# Top.net
KiCad netlist of a schematic drawn in Altium Designer
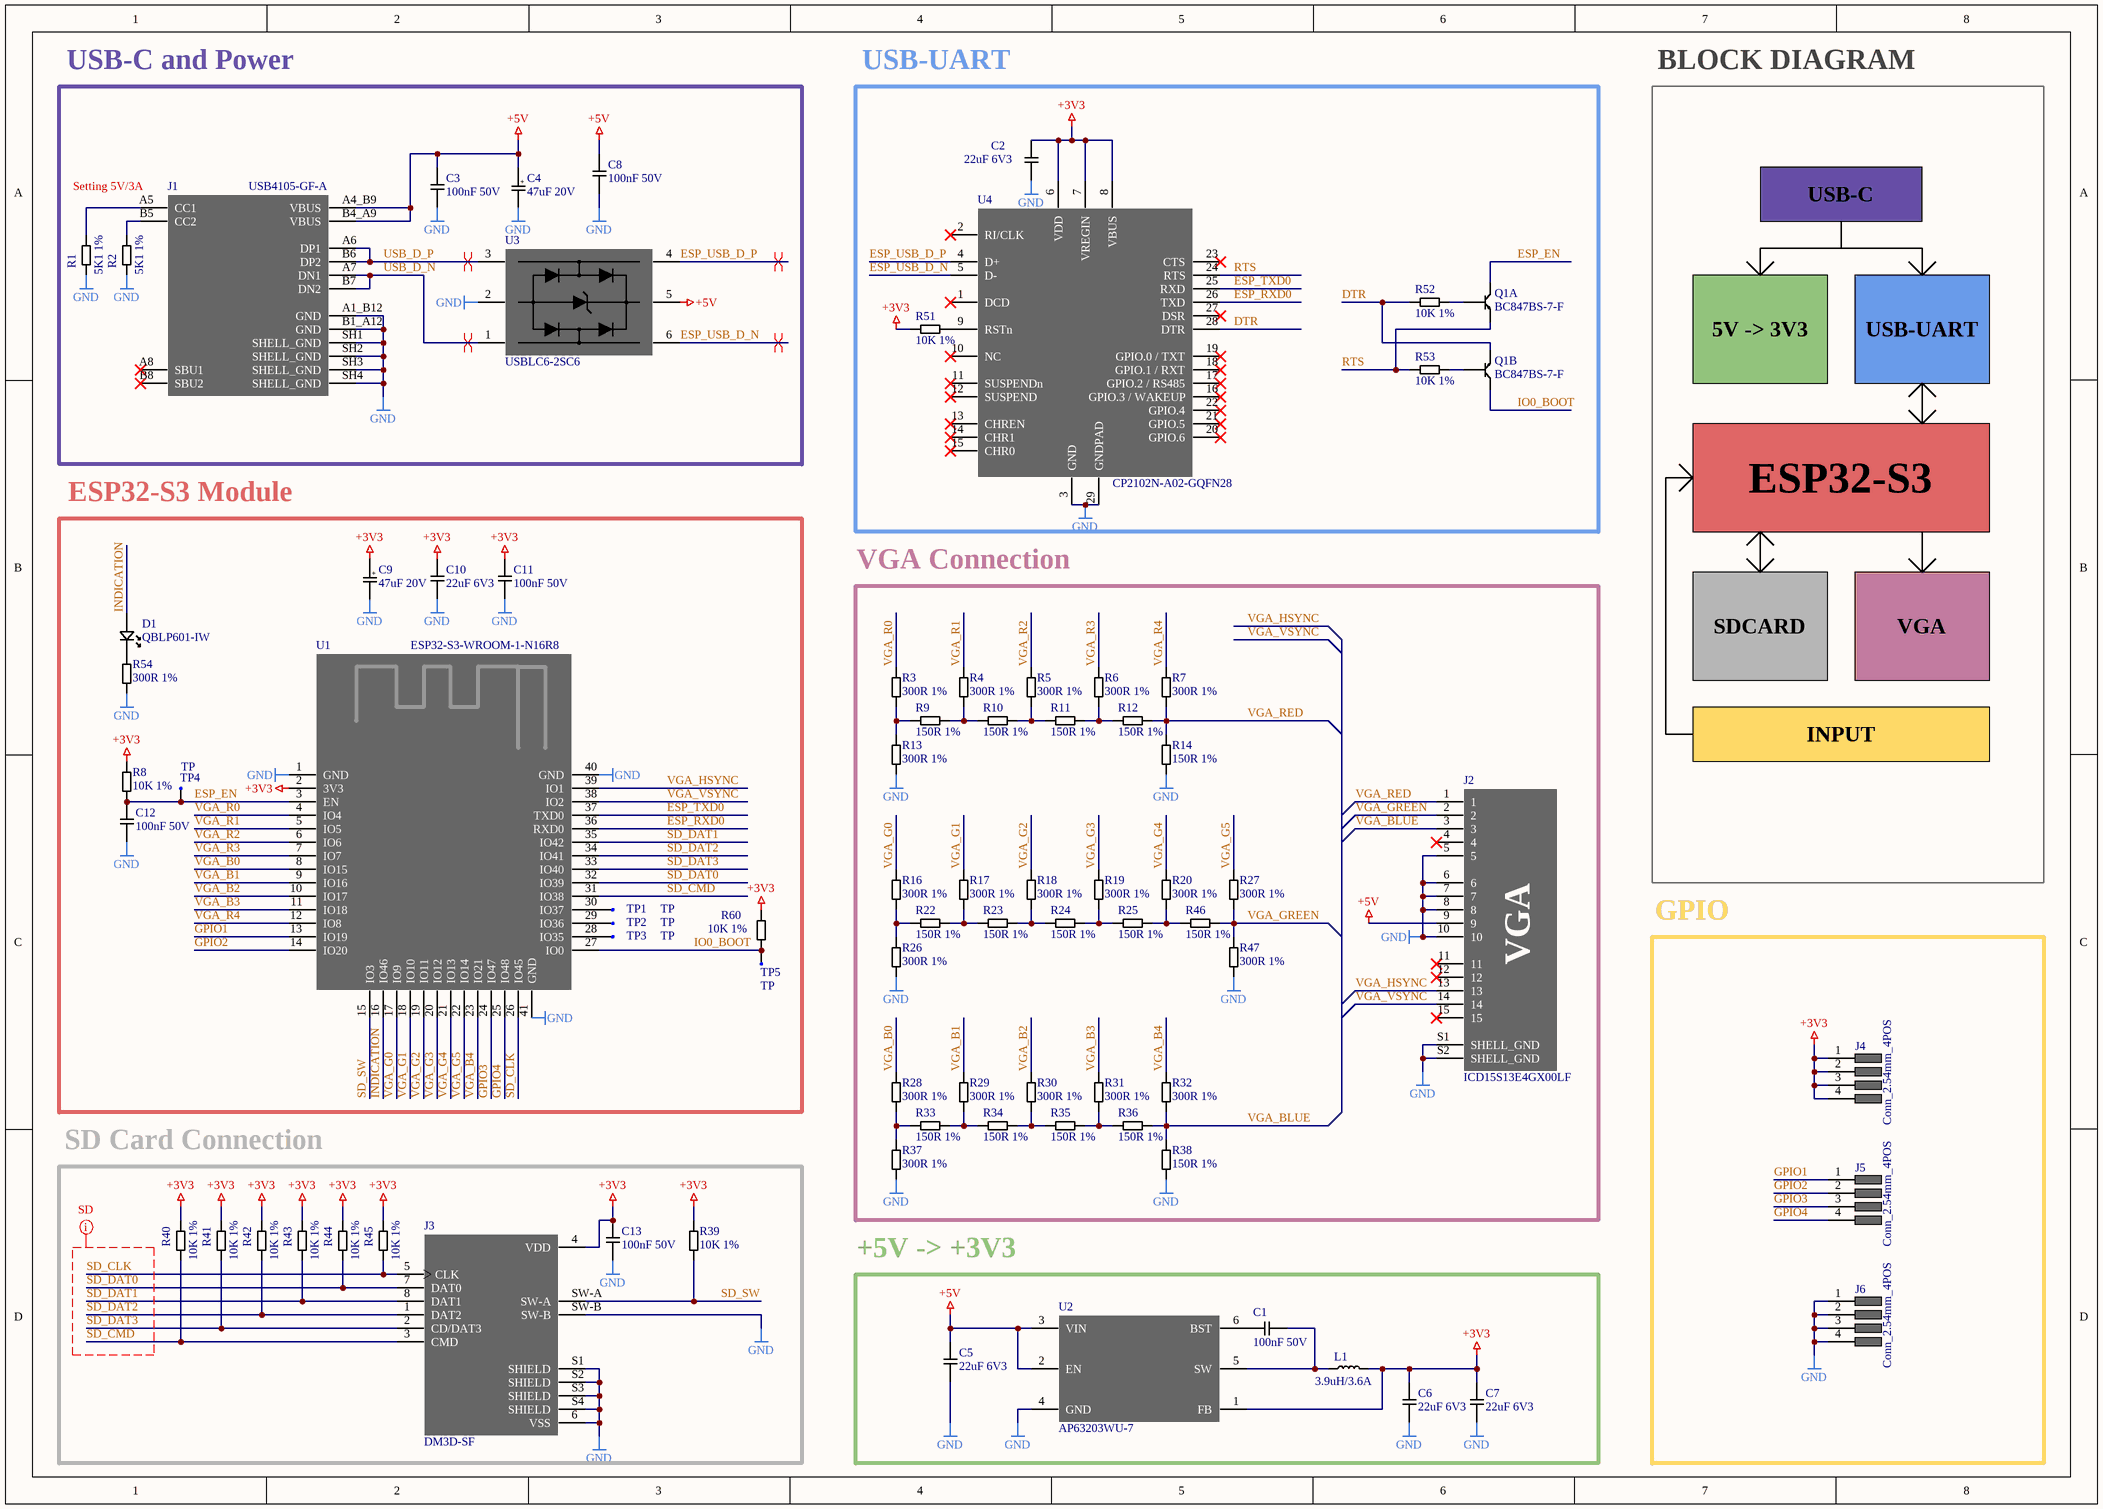
[diagram p0: Top.SchDoc]

(export (version "E")
  (design (tool "Eeschema 10.0.6"))
  (components
    (comp (ref "C1")
      (value "100nF 50V")
      (footprint "CAPC1608X06N")
      (description "0.1 µF ±10% 50V Ceramic Capacitor X7R 0603 (1608 Metric)")
      (fields (field (name "MPN") "GCM188R71H104KA57D"))
      (libsource (lib "VESA-ESP_LIB") (part "100nF 50V"))
    )
    (comp (ref "C2")
      (value "22uF 6V3")
      (footprint "CAPC1608X06N")
      (description "22 µF ±20% 6.3V Ceramic Capacitor X5R 0603 (1608 Metric)")
      (fields (field (name "MPN") "GRM188R60J226MEA0D"))
      (libsource (lib "VESA-ESP_LIB") (part "22uF 6V3"))
    )
    (comp (ref "C3")
      (value "100nF 50V")
      (footprint "CAPC1608X06N")
      (description "0.1 µF ±10% 50V Ceramic Capacitor X7R 0603 (1608 Metric)")
      (fields (field (name "MPN") "GCM188R71H104KA57D"))
      (libsource (lib "VESA-ESP_LIB") (part "100nF 50V"))
    )
    (comp (ref "C4")
      (value "47uF 20V")
      (footprint "865080342006")
      (description "47 µF 16 V Aluminum Electrolytic Capacitors Radial, Can - SMD 2000 Hrs @ 105°C")
      (libsource (lib "VESA-ESP_LIB") (part "47uF 20V"))
    )
    (comp (ref "C5")
      (value "22uF 6V3")
      (footprint "CAPC1608X06N")
      (description "22 µF ±20% 6.3V Ceramic Capacitor X5R 0603 (1608 Metric)")
      (fields (field (name "MPN") "GRM188R60J226MEA0D"))
      (libsource (lib "VESA-ESP_LIB") (part "22uF 6V3"))
    )
    (comp (ref "C6")
      (value "22uF 6V3")
      (footprint "CAPC1608X06N")
      (description "22 µF ±20% 6.3V Ceramic Capacitor X5R 0603 (1608 Metric)")
      (fields (field (name "MPN") "GRM188R60J226MEA0D"))
      (libsource (lib "VESA-ESP_LIB") (part "22uF 6V3"))
    )
    (comp (ref "C7")
      (value "22uF 6V3")
      (footprint "CAPC1608X06N")
      (description "22 µF ±20% 6.3V Ceramic Capacitor X5R 0603 (1608 Metric)")
      (fields (field (name "MPN") "GRM188R60J226MEA0D"))
      (libsource (lib "VESA-ESP_LIB") (part "22uF 6V3"))
    )
    (comp (ref "C8")
      (value "100nF 50V")
      (footprint "CAPC1608X06N")
      (description "0.1 µF ±10% 50V Ceramic Capacitor X7R 0603 (1608 Metric)")
      (fields (field (name "MPN") "GCM188R71H104KA57D"))
      (libsource (lib "VESA-ESP_LIB") (part "100nF 50V"))
    )
    (comp (ref "C9")
      (value "47uF 20V")
      (footprint "865080342006")
      (description "47 µF 16 V Aluminum Electrolytic Capacitors Radial, Can - SMD 2000 Hrs @ 105°C")
      (fields (field (name "MPN") "865080342006"))
      (libsource (lib "VESA-ESP_LIB") (part "47uF 20V"))
    )
    (comp (ref "C10")
      (value "22uF 6V3")
      (footprint "CAPC1608X06N")
      (description "22 µF ±20% 6.3V Ceramic Capacitor X5R 0603 (1608 Metric)")
      (fields (field (name "MPN") "GRM188R60J226MEA0D"))
      (libsource (lib "VESA-ESP_LIB") (part "22uF 6V3"))
    )
    (comp (ref "C11")
      (value "100nF 50V")
      (footprint "CAPC1608X06N")
      (description "0.1 µF ±10% 50V Ceramic Capacitor X7R 0603 (1608 Metric)")
      (fields (field (name "MPN") "GCM188R71H104KA57D"))
      (libsource (lib "VESA-ESP_LIB") (part "100nF 50V"))
    )
    (comp (ref "C12")
      (value "100nF 50V")
      (footprint "CAPC1608X06N")
      (description "0.1 µF ±10% 50V Ceramic Capacitor X7R 0603 (1608 Metric)")
      (fields (field (name "MPN") "GCM188R71H104KA57D"))
      (libsource (lib "VESA-ESP_LIB") (part "100nF 50V"))
    )
    (comp (ref "C13")
      (value "100nF 50V")
      (footprint "CAPC1608X06N")
      (description "0.1 µF ±10% 50V Ceramic Capacitor X7R 0603 (1608 Metric)")
      (fields (field (name "MPN") "GCM188R71H104KA57D"))
      (libsource (lib "VESA-ESP_LIB") (part "100nF 50V"))
    )
    (comp (ref "D1")
      (value "QBLP601-IW")
      (footprint "LEDC1608X06N")
      (description "White LED Indication - Discrete 3.2V 0603 (1608 Metric)")
      (libsource (lib "VESA-ESP_LIB") (part "LED WHITE"))
    )
    (comp (ref "J1")
      (value "USB4105-GF-A")
      (footprint "USB4105-GF-A")
      (libsource (lib "VESA-ESP_LIB") (part "USB4105-GF-A"))
    )
    (comp (ref "J2")
      (value "ICD15S13E4GX00LF")
      (footprint "ICD15S13E4GX00LF")
      (description "15 Position D-Sub, High Density Receptacle, Female Sockets Connector")
      (libsource (lib "VESA-ESP_LIB") (part "ICD15S13E4GX00LF"))
    )
    (comp (ref "J3")
      (value "DM3D-SF")
      (footprint "DM3D-SF")
      (description "10 (8 + 2) Position Card Connector Secure Digital - microSD™ Surface Mount, Right Angle Gold")
      (libsource (lib "VESA-ESP_LIB") (part "DM3D-SF"))
    )
    (comp (ref "J4")
      (value "Conn_2.54mm_4POS")
      (footprint "CONN_2.54MM_4POS")
      (libsource (lib "VESA-ESP_LIB") (part "Conn_2.54mm_4POS_1"))
    )
    (comp (ref "J5")
      (value "Conn_2.54mm_4POS")
      (footprint "CONN_2.54MM_4POS")
      (libsource (lib "VESA-ESP_LIB") (part "Conn_2.54mm_4POS_1"))
    )
    (comp (ref "J6")
      (value "Conn_2.54mm_4POS")
      (footprint "CONN_2.54MM_4POS")
      (libsource (lib "VESA-ESP_LIB") (part "Conn_2.54mm_4POS_1"))
    )
    (comp (ref "L1")
      (value "3.9uH/3.6A")
      (footprint "SDE0604A-3R9M")
      (description "FIXED IND 3.9UH 3.6A 65 MOHM SMD")
      (fields (field (name "MPN") "SDE0604A-3R9M"))
      (libsource (lib "VESA-ESP_LIB") (part "3.9uH/3.6A"))
    )
    (comp (ref "Q1")
      (value "BC847BS-7-F")
      (footprint "SOT65P210X110-6N")
      (description "Bipolar (BJT) Transistor Array 2 NPN (Dual) 45V 100mA 100MHz 200mW Surface Mount SOT-363")
      (libsource (lib "VESA-ESP_LIB") (part "BC847BS-7-F"))
    )
    (comp (ref "R1")
      (value "5K1 1%")
      (footprint "RESC1608X06N")
      (description "5.1 kOhms ±1% 0.1W, 1/10W Chip Resistor 0603 (1608 Metric) Automotive AEC-Q200 Thick Film")
      (fields (field (name "MPN") "ERJ-3EKF5101V"))
      (libsource (lib "VESA-ESP_LIB") (part "5K1 1%"))
    )
    (comp (ref "R2")
      (value "5K1 1%")
      (footprint "RESC1608X06N")
      (description "5.1 kOhms ±1% 0.1W, 1/10W Chip Resistor 0603 (1608 Metric) Automotive AEC-Q200 Thick Film")
      (fields (field (name "MPN") "ERJ-3EKF5101V"))
      (libsource (lib "VESA-ESP_LIB") (part "5K1 1%"))
    )
    (comp (ref "R3")
      (value "300R 1%")
      (footprint "RESC1608X06N")
      (description "300 Ohms ±1% 0.1W, 1/10W Chip Resistor 0603 (1608 Metric) Automotive AEC-Q200 Thick Film")
      (fields (field (name "MPN") "ERJ-3EKF3000V"))
      (libsource (lib "VESA-ESP_LIB") (part "300R 1%"))
    )
    (comp (ref "R4")
      (value "300R 1%")
      (footprint "RESC1608X06N")
      (description "300 Ohms ±1% 0.1W, 1/10W Chip Resistor 0603 (1608 Metric) Automotive AEC-Q200 Thick Film")
      (fields (field (name "MPN") "ERJ-3EKF3000V"))
      (libsource (lib "VESA-ESP_LIB") (part "300R 1%"))
    )
    (comp (ref "R5")
      (value "300R 1%")
      (footprint "RESC1608X06N")
      (description "300 Ohms ±1% 0.1W, 1/10W Chip Resistor 0603 (1608 Metric) Automotive AEC-Q200 Thick Film")
      (fields (field (name "MPN") "ERJ-3EKF3000V"))
      (libsource (lib "VESA-ESP_LIB") (part "300R 1%"))
    )
    (comp (ref "R6")
      (value "300R 1%")
      (footprint "RESC1608X06N")
      (description "300 Ohms ±1% 0.1W, 1/10W Chip Resistor 0603 (1608 Metric) Automotive AEC-Q200 Thick Film")
      (fields (field (name "MPN") "ERJ-3EKF3000V"))
      (libsource (lib "VESA-ESP_LIB") (part "300R 1%"))
    )
    (comp (ref "R7")
      (value "300R 1%")
      (footprint "RESC1608X06N")
      (description "300 Ohms ±1% 0.1W, 1/10W Chip Resistor 0603 (1608 Metric) Automotive AEC-Q200 Thick Film")
      (fields (field (name "MPN") "ERJ-3EKF3000V"))
      (libsource (lib "VESA-ESP_LIB") (part "300R 1%"))
    )
    (comp (ref "R8")
      (value "10K 1%")
      (footprint "RESC1608X06N")
      (description "10 kOhms ±1% 0.1W, 1/10W Chip Resistor 0603 (1608 Metric) Automotive AEC-Q200 Thick Film")
      (fields (field (name "MPN") "ERJ-3EKF1002V"))
      (libsource (lib "VESA-ESP_LIB") (part "10K 1%"))
    )
    (comp (ref "R9")
      (value "150R 1%")
      (footprint "RESC1608X06N")
      (description "150 Ohms ±1% 0.1W, 1/10W Chip Resistor 0603 (1608 Metric) Automotive AEC-Q200 Thick Film")
      (fields (field (name "MPN") "ERJ-3EKF1500V"))
      (libsource (lib "VESA-ESP_LIB") (part "150R 1%"))
    )
    (comp (ref "R10")
      (value "150R 1%")
      (footprint "RESC1608X06N")
      (description "150 Ohms ±1% 0.1W, 1/10W Chip Resistor 0603 (1608 Metric) Automotive AEC-Q200 Thick Film")
      (fields (field (name "MPN") "ERJ-3EKF1500V"))
      (libsource (lib "VESA-ESP_LIB") (part "150R 1%"))
    )
    (comp (ref "R11")
      (value "150R 1%")
      (footprint "RESC1608X06N")
      (description "150 Ohms ±1% 0.1W, 1/10W Chip Resistor 0603 (1608 Metric) Automotive AEC-Q200 Thick Film")
      (fields (field (name "MPN") "ERJ-3EKF1500V"))
      (libsource (lib "VESA-ESP_LIB") (part "150R 1%"))
    )
    (comp (ref "R12")
      (value "150R 1%")
      (footprint "RESC1608X06N")
      (description "150 Ohms ±1% 0.1W, 1/10W Chip Resistor 0603 (1608 Metric) Automotive AEC-Q200 Thick Film")
      (fields (field (name "MPN") "ERJ-3EKF1500V"))
      (libsource (lib "VESA-ESP_LIB") (part "150R 1%"))
    )
    (comp (ref "R13")
      (value "300R 1%")
      (footprint "RESC1608X06N")
      (description "300 Ohms ±1% 0.1W, 1/10W Chip Resistor 0603 (1608 Metric) Automotive AEC-Q200 Thick Film")
      (fields (field (name "MPN") "ERJ-3EKF3000V"))
      (libsource (lib "VESA-ESP_LIB") (part "300R 1%"))
    )
    (comp (ref "R14")
      (value "150R 1%")
      (footprint "RESC1608X06N")
      (description "150 Ohms ±1% 0.1W, 1/10W Chip Resistor 0603 (1608 Metric) Automotive AEC-Q200 Thick Film")
      (fields (field (name "MPN") "ERJ-3EKF1500V"))
      (libsource (lib "VESA-ESP_LIB") (part "150R 1%"))
    )
    (comp (ref "R16")
      (value "300R 1%")
      (footprint "RESC1608X06N")
      (description "300 Ohms ±1% 0.1W, 1/10W Chip Resistor 0603 (1608 Metric) Automotive AEC-Q200 Thick Film")
      (fields (field (name "MPN") "ERJ-3EKF3000V"))
      (libsource (lib "VESA-ESP_LIB") (part "300R 1%"))
    )
    (comp (ref "R17")
      (value "300R 1%")
      (footprint "RESC1608X06N")
      (description "300 Ohms ±1% 0.1W, 1/10W Chip Resistor 0603 (1608 Metric) Automotive AEC-Q200 Thick Film")
      (fields (field (name "MPN") "ERJ-3EKF3000V"))
      (libsource (lib "VESA-ESP_LIB") (part "300R 1%"))
    )
    (comp (ref "R18")
      (value "300R 1%")
      (footprint "RESC1608X06N")
      (description "300 Ohms ±1% 0.1W, 1/10W Chip Resistor 0603 (1608 Metric) Automotive AEC-Q200 Thick Film")
      (fields (field (name "MPN") "ERJ-3EKF3000V"))
      (libsource (lib "VESA-ESP_LIB") (part "300R 1%"))
    )
    (comp (ref "R19")
      (value "300R 1%")
      (footprint "RESC1608X06N")
      (description "300 Ohms ±1% 0.1W, 1/10W Chip Resistor 0603 (1608 Metric) Automotive AEC-Q200 Thick Film")
      (fields (field (name "MPN") "ERJ-3EKF3000V"))
      (libsource (lib "VESA-ESP_LIB") (part "300R 1%"))
    )
    (comp (ref "R20")
      (value "300R 1%")
      (footprint "RESC1608X06N")
      (description "300 Ohms ±1% 0.1W, 1/10W Chip Resistor 0603 (1608 Metric) Automotive AEC-Q200 Thick Film")
      (fields (field (name "MPN") "ERJ-3EKF3000V"))
      (libsource (lib "VESA-ESP_LIB") (part "300R 1%"))
    )
    (comp (ref "R22")
      (value "150R 1%")
      (footprint "RESC1608X06N")
      (description "150 Ohms ±1% 0.1W, 1/10W Chip Resistor 0603 (1608 Metric) Automotive AEC-Q200 Thick Film")
      (fields (field (name "MPN") "ERJ-3EKF1500V"))
      (libsource (lib "VESA-ESP_LIB") (part "150R 1%"))
    )
    (comp (ref "R23")
      (value "150R 1%")
      (footprint "RESC1608X06N")
      (description "150 Ohms ±1% 0.1W, 1/10W Chip Resistor 0603 (1608 Metric) Automotive AEC-Q200 Thick Film")
      (fields (field (name "MPN") "ERJ-3EKF1500V"))
      (libsource (lib "VESA-ESP_LIB") (part "150R 1%"))
    )
    (comp (ref "R24")
      (value "150R 1%")
      (footprint "RESC1608X06N")
      (description "150 Ohms ±1% 0.1W, 1/10W Chip Resistor 0603 (1608 Metric) Automotive AEC-Q200 Thick Film")
      (fields (field (name "MPN") "ERJ-3EKF1500V"))
      (libsource (lib "VESA-ESP_LIB") (part "150R 1%"))
    )
    (comp (ref "R25")
      (value "150R 1%")
      (footprint "RESC1608X06N")
      (description "150 Ohms ±1% 0.1W, 1/10W Chip Resistor 0603 (1608 Metric) Automotive AEC-Q200 Thick Film")
      (fields (field (name "MPN") "ERJ-3EKF1500V"))
      (libsource (lib "VESA-ESP_LIB") (part "150R 1%"))
    )
    (comp (ref "R26")
      (value "300R 1%")
      (footprint "RESC1608X06N")
      (description "300 Ohms ±1% 0.1W, 1/10W Chip Resistor 0603 (1608 Metric) Automotive AEC-Q200 Thick Film")
      (fields (field (name "MPN") "ERJ-3EKF3000V"))
      (libsource (lib "VESA-ESP_LIB") (part "300R 1%"))
    )
    (comp (ref "R27")
      (value "300R 1%")
      (footprint "RESC1608X06N")
      (description "300 Ohms ±1% 0.1W, 1/10W Chip Resistor 0603 (1608 Metric) Automotive AEC-Q200 Thick Film")
      (fields (field (name "MPN") "ERJ-3EKF3000V"))
      (libsource (lib "VESA-ESP_LIB") (part "300R 1%"))
    )
    (comp (ref "R28")
      (value "300R 1%")
      (footprint "RESC1608X06N")
      (description "300 Ohms ±1% 0.1W, 1/10W Chip Resistor 0603 (1608 Metric) Automotive AEC-Q200 Thick Film")
      (fields (field (name "MPN") "ERJ-3EKF3000V"))
      (libsource (lib "VESA-ESP_LIB") (part "300R 1%"))
    )
    (comp (ref "R29")
      (value "300R 1%")
      (footprint "RESC1608X06N")
      (description "300 Ohms ±1% 0.1W, 1/10W Chip Resistor 0603 (1608 Metric) Automotive AEC-Q200 Thick Film")
      (fields (field (name "MPN") "ERJ-3EKF3000V"))
      (libsource (lib "VESA-ESP_LIB") (part "300R 1%"))
    )
    (comp (ref "R30")
      (value "300R 1%")
      (footprint "RESC1608X06N")
      (description "300 Ohms ±1% 0.1W, 1/10W Chip Resistor 0603 (1608 Metric) Automotive AEC-Q200 Thick Film")
      (fields (field (name "MPN") "ERJ-3EKF3000V"))
      (libsource (lib "VESA-ESP_LIB") (part "300R 1%"))
    )
    (comp (ref "R31")
      (value "300R 1%")
      (footprint "RESC1608X06N")
      (description "300 Ohms ±1% 0.1W, 1/10W Chip Resistor 0603 (1608 Metric) Automotive AEC-Q200 Thick Film")
      (fields (field (name "MPN") "ERJ-3EKF3000V"))
      (libsource (lib "VESA-ESP_LIB") (part "300R 1%"))
    )
    (comp (ref "R32")
      (value "300R 1%")
      (footprint "RESC1608X06N")
      (description "300 Ohms ±1% 0.1W, 1/10W Chip Resistor 0603 (1608 Metric) Automotive AEC-Q200 Thick Film")
      (fields (field (name "MPN") "ERJ-3EKF3000V"))
      (libsource (lib "VESA-ESP_LIB") (part "300R 1%"))
    )
    (comp (ref "R33")
      (value "150R 1%")
      (footprint "RESC1608X06N")
      (description "150 Ohms ±1% 0.1W, 1/10W Chip Resistor 0603 (1608 Metric) Automotive AEC-Q200 Thick Film")
      (fields (field (name "MPN") "ERJ-3EKF1500V"))
      (libsource (lib "VESA-ESP_LIB") (part "150R 1%"))
    )
    (comp (ref "R34")
      (value "150R 1%")
      (footprint "RESC1608X06N")
      (description "150 Ohms ±1% 0.1W, 1/10W Chip Resistor 0603 (1608 Metric) Automotive AEC-Q200 Thick Film")
      (fields (field (name "MPN") "ERJ-3EKF1500V"))
      (libsource (lib "VESA-ESP_LIB") (part "150R 1%"))
    )
    (comp (ref "R35")
      (value "150R 1%")
      (footprint "RESC1608X06N")
      (description "150 Ohms ±1% 0.1W, 1/10W Chip Resistor 0603 (1608 Metric) Automotive AEC-Q200 Thick Film")
      (fields (field (name "MPN") "ERJ-3EKF1500V"))
      (libsource (lib "VESA-ESP_LIB") (part "150R 1%"))
    )
    (comp (ref "R36")
      (value "150R 1%")
      (footprint "RESC1608X06N")
      (description "150 Ohms ±1% 0.1W, 1/10W Chip Resistor 0603 (1608 Metric) Automotive AEC-Q200 Thick Film")
      (fields (field (name "MPN") "ERJ-3EKF1500V"))
      (libsource (lib "VESA-ESP_LIB") (part "150R 1%"))
    )
    (comp (ref "R37")
      (value "300R 1%")
      (footprint "RESC1608X06N")
      (description "300 Ohms ±1% 0.1W, 1/10W Chip Resistor 0603 (1608 Metric) Automotive AEC-Q200 Thick Film")
      (fields (field (name "MPN") "ERJ-3EKF3000V"))
      (libsource (lib "VESA-ESP_LIB") (part "300R 1%"))
    )
    (comp (ref "R38")
      (value "150R 1%")
      (footprint "RESC1608X06N")
      (description "150 Ohms ±1% 0.1W, 1/10W Chip Resistor 0603 (1608 Metric) Automotive AEC-Q200 Thick Film")
      (fields (field (name "MPN") "ERJ-3EKF1500V"))
      (libsource (lib "VESA-ESP_LIB") (part "150R 1%"))
    )
    (comp (ref "R39")
      (value "10K 1%")
      (footprint "RESC1608X06N")
      (description "10 kOhms ±1% 0.1W, 1/10W Chip Resistor 0603 (1608 Metric) Automotive AEC-Q200 Thick Film")
      (fields (field (name "MPN") "ERJ-3EKF1002V"))
      (libsource (lib "VESA-ESP_LIB") (part "10K 1%"))
    )
    (comp (ref "R40")
      (value "10K 1%")
      (footprint "RESC1608X06N")
      (description "10 kOhms ±1% 0.1W, 1/10W Chip Resistor 0603 (1608 Metric) Automotive AEC-Q200 Thick Film")
      (fields (field (name "MPN") "ERJ-3EKF1002V"))
      (libsource (lib "VESA-ESP_LIB") (part "10K 1%"))
    )
    (comp (ref "R41")
      (value "10K 1%")
      (footprint "RESC1608X06N")
      (description "10 kOhms ±1% 0.1W, 1/10W Chip Resistor 0603 (1608 Metric) Automotive AEC-Q200 Thick Film")
      (fields (field (name "MPN") "ERJ-3EKF1002V"))
      (libsource (lib "VESA-ESP_LIB") (part "10K 1%"))
    )
    (comp (ref "R42")
      (value "10K 1%")
      (footprint "RESC1608X06N")
      (description "10 kOhms ±1% 0.1W, 1/10W Chip Resistor 0603 (1608 Metric) Automotive AEC-Q200 Thick Film")
      (fields (field (name "MPN") "ERJ-3EKF1002V"))
      (libsource (lib "VESA-ESP_LIB") (part "10K 1%"))
    )
    (comp (ref "R43")
      (value "10K 1%")
      (footprint "RESC1608X06N")
      (description "10 kOhms ±1% 0.1W, 1/10W Chip Resistor 0603 (1608 Metric) Automotive AEC-Q200 Thick Film")
      (fields (field (name "MPN") "ERJ-3EKF1002V"))
      (libsource (lib "VESA-ESP_LIB") (part "10K 1%"))
    )
    (comp (ref "R44")
      (value "10K 1%")
      (footprint "RESC1608X06N")
      (description "10 kOhms ±1% 0.1W, 1/10W Chip Resistor 0603 (1608 Metric) Automotive AEC-Q200 Thick Film")
      (fields (field (name "MPN") "ERJ-3EKF1002V"))
      (libsource (lib "VESA-ESP_LIB") (part "10K 1%"))
    )
    (comp (ref "R45")
      (value "10K 1%")
      (footprint "RESC1608X06N")
      (description "10 kOhms ±1% 0.1W, 1/10W Chip Resistor 0603 (1608 Metric) Automotive AEC-Q200 Thick Film")
      (fields (field (name "MPN") "ERJ-3EKF1002V"))
      (libsource (lib "VESA-ESP_LIB") (part "10K 1%"))
    )
    (comp (ref "R46")
      (value "150R 1%")
      (footprint "RESC1608X06N")
      (description "150 Ohms ±1% 0.1W, 1/10W Chip Resistor 0603 (1608 Metric) Automotive AEC-Q200 Thick Film")
      (fields (field (name "MPN") "ERJ-3EKF1500V"))
      (libsource (lib "VESA-ESP_LIB") (part "150R 1%"))
    )
    (comp (ref "R47")
      (value "300R 1%")
      (footprint "RESC1608X06N")
      (description "300 Ohms ±1% 0.1W, 1/10W Chip Resistor 0603 (1608 Metric) Automotive AEC-Q200 Thick Film")
      (fields (field (name "MPN") "ERJ-3EKF3000V"))
      (libsource (lib "VESA-ESP_LIB") (part "300R 1%"))
    )
    (comp (ref "R51")
      (value "10K 1%")
      (footprint "RESC1608X06N")
      (description "10 kOhms ±1% 0.1W, 1/10W Chip Resistor 0603 (1608 Metric) Automotive AEC-Q200 Thick Film")
      (fields (field (name "MPN") "ERJ-3EKF1002V"))
      (libsource (lib "VESA-ESP_LIB") (part "10K 1%"))
    )
    (comp (ref "R52")
      (value "10K 1%")
      (footprint "RESC1608X06N")
      (description "10 kOhms ±1% 0.1W, 1/10W Chip Resistor 0603 (1608 Metric) Automotive AEC-Q200 Thick Film")
      (fields (field (name "MPN") "ERJ-3EKF1002V"))
      (libsource (lib "VESA-ESP_LIB") (part "10K 1%"))
    )
    (comp (ref "R53")
      (value "10K 1%")
      (footprint "RESC1608X06N")
      (description "10 kOhms ±1% 0.1W, 1/10W Chip Resistor 0603 (1608 Metric) Automotive AEC-Q200 Thick Film")
      (fields (field (name "MPN") "ERJ-3EKF1002V"))
      (libsource (lib "VESA-ESP_LIB") (part "10K 1%"))
    )
    (comp (ref "R54")
      (value "300R 1%")
      (footprint "RESC1608X06N")
      (description "300 Ohms ±1% 0.1W, 1/10W Chip Resistor 0603 (1608 Metric) Automotive AEC-Q200 Thick Film")
      (fields (field (name "MPN") "ERJ-3EKF3000V"))
      (libsource (lib "VESA-ESP_LIB") (part "300R 1%"))
    )
    (comp (ref "R60")
      (value "10K 1%")
      (footprint "RESC1608X06N")
      (description "10 kOhms ±1% 0.1W, 1/10W Chip Resistor 0603 (1608 Metric) Automotive AEC-Q200 Thick Film")
      (fields (field (name "MPN") "ERJ-3EKF1002V"))
      (libsource (lib "VESA-ESP_LIB") (part "10K 1%"))
    )
    (comp (ref "TP1")
      (value "TP")
      (footprint "TESTPOINT")
      (description "Test Point")
      (libsource (lib "VESA-ESP_LIB") (part "TP"))
    )
    (comp (ref "TP2")
      (value "TP")
      (footprint "TESTPOINT")
      (description "Test Point")
      (libsource (lib "VESA-ESP_LIB") (part "TP"))
    )
    (comp (ref "TP3")
      (value "TP")
      (footprint "TESTPOINT")
      (description "Test Point")
      (libsource (lib "VESA-ESP_LIB") (part "TP"))
    )
    (comp (ref "TP4")
      (value "TP")
      (footprint "TESTPOINT")
      (description "Test Point")
      (libsource (lib "VESA-ESP_LIB") (part "TP"))
    )
    (comp (ref "TP5")
      (value "TP")
      (footprint "TESTPOINT")
      (description "Test Point")
      (libsource (lib "VESA-ESP_LIB") (part "TP"))
    )
    (comp (ref "U1")
      (value "ESP32-S3-WROOM-1-N16R8")
      (footprint "ESP32-S3-WROOM")
      (description "Bluetooth, WiFi 802.11b/g/n, Bluetooth v5.0 Transceiver Module 2.4GHz PCB Trace Surface Mount")
      (libsource (lib "VESA-ESP_LIB") (part "ESP32-S3-WROOM-1-N16R8"))
    )
    (comp (ref "U2")
      (value "AP63203WU-7")
      (footprint "SOT95P245X100-6N")
      (description "Buck Switching Regulator IC Positive Fixed 3.3V 1 Output 2A SOT-23-6 Thin, TSOT-23-6")
      (libsource (lib "VESA-ESP_LIB") (part "AP63203WU-7"))
    )
    (comp (ref "U3")
      (value "USBLC6-2SC6")
      (footprint "SOT95P245X100-6N")
      (description "17V Clamp 5A (8/20µs) Ipp Tvs Diode Surface Mount SOT-23-6")
      (libsource (lib "VESA-ESP_LIB") (part "USBLC6-2SC6"))
    )
    (comp (ref "U4")
      (value "CP2102N-A02-GQFN28")
      (footprint "QFN50P500X500X80-29N")
      (description "USB Bridge, USB to UART USB 2.0 UART Interface 28-QFN (5x5)")
      (libsource (lib "VESA-ESP_LIB") (part "CP2102N-A02-GQFN28"))
    )
  )
  (nets
    (net (code "1") (name "+3V3") (class "Default")
      (node (ref "C10") (pin "2") (pinfunction "2_2") (pintype "passive"))
      (node (ref "C11") (pin "2") (pinfunction "2_2") (pintype "passive"))
      (node (ref "C13") (pin "2") (pinfunction "2_2") (pintype "passive"))
      (node (ref "C2") (pin "2") (pinfunction "2_2") (pintype "passive"))
      (node (ref "C6") (pin "2") (pinfunction "2_2") (pintype "passive"))
      (node (ref "C7") (pin "2") (pinfunction "2_2") (pintype "passive"))
      (node (ref "C9") (pin "1") (pinfunction "1_1") (pintype "passive"))
      (node (ref "J3") (pin "4") (pinfunction "VDD_4") (pintype "passive"))
      (node (ref "J4") (pin "1") (pinfunction "1_1") (pintype "passive"))
      (node (ref "J4") (pin "2") (pinfunction "2_2") (pintype "passive"))
      (node (ref "J4") (pin "3") (pinfunction "3_3") (pintype "passive"))
      (node (ref "J4") (pin "4") (pinfunction "4_4") (pintype "passive"))
      (node (ref "L1") (pin "2") (pinfunction "2_2") (pintype "passive"))
      (node (ref "R39") (pin "1") (pinfunction "1_1") (pintype "passive"))
      (node (ref "R40") (pin "1") (pinfunction "1_1") (pintype "passive"))
      (node (ref "R41") (pin "1") (pinfunction "1_1") (pintype "passive"))
      (node (ref "R42") (pin "1") (pinfunction "1_1") (pintype "passive"))
      (node (ref "R43") (pin "1") (pinfunction "1_1") (pintype "passive"))
      (node (ref "R44") (pin "1") (pinfunction "1_1") (pintype "passive"))
      (node (ref "R45") (pin "1") (pinfunction "1_1") (pintype "passive"))
      (node (ref "R51") (pin "1") (pinfunction "1_1") (pintype "passive"))
      (node (ref "R60") (pin "1") (pinfunction "1_1") (pintype "passive"))
      (node (ref "R8") (pin "1") (pinfunction "1_1") (pintype "passive"))
      (node (ref "U1") (pin "2") (pinfunction "3V3_2") (pintype "passive"))
      (node (ref "U2") (pin "1") (pinfunction "FB_1") (pintype "passive"))
      (node (ref "U4") (pin "6") (pinfunction "VDD_6") (pintype "passive"))
      (node (ref "U4") (pin "7") (pinfunction "VREGIN_7") (pintype "passive"))
      (node (ref "U4") (pin "8") (pinfunction "VBUS_8") (pintype "passive"))
    )
    (net (code "2") (name "+5V") (class "Default")
      (node (ref "C3") (pin "2") (pinfunction "2_2") (pintype "passive"))
      (node (ref "C4") (pin "1") (pinfunction "1_1") (pintype "passive"))
      (node (ref "C5") (pin "2") (pinfunction "2_2") (pintype "passive"))
      (node (ref "C8") (pin "2") (pinfunction "2_2") (pintype "passive"))
      (node (ref "J1") (pin "A4_B9") (pinfunction "VBUS_A4_B9") (pintype "passive"))
      (node (ref "J1") (pin "B4_A9") (pinfunction "VBUS_B4_A9") (pintype "passive"))
      (node (ref "J2") (pin "9") (pinfunction "9_9") (pintype "passive"))
      (node (ref "U2") (pin "2") (pinfunction "EN_2") (pintype "passive"))
      (node (ref "U2") (pin "3") (pinfunction "VIN_3") (pintype "passive"))
      (node (ref "U3") (pin "5") (pinfunction "5_5") (pintype "passive"))
    )
    (net (code "3") (name "/DTR") (class "Default")
      (node (ref "Q1") (pin "1") (pinfunction "1_1") (pintype "passive"))
      (node (ref "R52") (pin "2") (pinfunction "2_2") (pintype "passive"))
      (node (ref "U4") (pin "28") (pinfunction "DTR_28") (pintype "passive"))
    )
    (net (code "4") (name "/ESP_EN") (class "Default")
      (node (ref "C12") (pin "2") (pinfunction "2_2") (pintype "passive"))
      (node (ref "Q1") (pin "3") (pinfunction "3_3") (pintype "passive"))
      (node (ref "R8") (pin "2") (pinfunction "2_2") (pintype "passive"))
      (node (ref "TP4") (pin "1") (pinfunction "1_1") (pintype "passive"))
      (node (ref "U1") (pin "3") (pinfunction "EN_3") (pintype "passive"))
    )
    (net (code "5") (name "/ESP_RXD0") (class "Default")
      (node (ref "U1") (pin "36") (pinfunction "RXD0_36") (pintype "passive"))
      (node (ref "U4") (pin "26") (pinfunction "TXD_26") (pintype "passive"))
    )
    (net (code "6") (name "/ESP_TXD0") (class "Default")
      (node (ref "U1") (pin "37") (pinfunction "TXD0_37") (pintype "passive"))
      (node (ref "U4") (pin "25") (pinfunction "RXD_25") (pintype "passive"))
    )
    (net (code "7") (name "/ESP_USB_D_N") (class "Default")
      (node (ref "U3") (pin "6") (pinfunction "6_6") (pintype "passive"))
      (node (ref "U4") (pin "5") (pinfunction "D-_5") (pintype "passive"))
    )
    (net (code "8") (name "/ESP_USB_D_P") (class "Default")
      (node (ref "U3") (pin "4") (pinfunction "4_4") (pintype "passive"))
      (node (ref "U4") (pin "4") (pinfunction "D+_4") (pintype "passive"))
    )
    (net (code "9") (name "/GPIO1") (class "Default")
      (node (ref "J5") (pin "1") (pinfunction "1_1") (pintype "passive"))
      (node (ref "U1") (pin "13") (pinfunction "IO19_13") (pintype "passive"))
    )
    (net (code "10") (name "/GPIO2") (class "Default")
      (node (ref "J5") (pin "2") (pinfunction "2_2") (pintype "passive"))
      (node (ref "U1") (pin "14") (pinfunction "IO20_14") (pintype "passive"))
    )
    (net (code "11") (name "/GPIO3") (class "Default")
      (node (ref "J5") (pin "3") (pinfunction "3_3") (pintype "passive"))
      (node (ref "U1") (pin "24") (pinfunction "IO47_24") (pintype "passive"))
    )
    (net (code "12") (name "/GPIO4") (class "Default")
      (node (ref "J5") (pin "4") (pinfunction "4_4") (pintype "passive"))
      (node (ref "U1") (pin "25") (pinfunction "IO48_25") (pintype "passive"))
    )
    (net (code "13") (name "/INDICATION") (class "Default")
      (node (ref "D1") (pin "1") (pinfunction "1_1") (pintype "passive"))
      (node (ref "U1") (pin "16") (pinfunction "IO46_16") (pintype "passive"))
    )
    (net (code "14") (name "/IO0_BOOT") (class "Default")
      (node (ref "Q1") (pin "6") (pinfunction "6_6") (pintype "passive"))
      (node (ref "R60") (pin "2") (pinfunction "2_2") (pintype "passive"))
      (node (ref "TP5") (pin "1") (pinfunction "1_1") (pintype "passive"))
      (node (ref "U1") (pin "27") (pinfunction "IO0_27") (pintype "passive"))
    )
    (net (code "15") (name "/RTS") (class "Default")
      (node (ref "Q1") (pin "4") (pinfunction "4_4") (pintype "passive"))
      (node (ref "R53") (pin "2") (pinfunction "2_2") (pintype "passive"))
      (node (ref "U4") (pin "24") (pinfunction "RTS_24") (pintype "passive"))
    )
    (net (code "16") (name "/SD_CLK") (class "Default")
      (node (ref "J3") (pin "5") (pinfunction "CLK_5") (pintype "passive"))
      (node (ref "R45") (pin "2") (pinfunction "2_2") (pintype "passive"))
      (node (ref "U1") (pin "26") (pinfunction "IO45_26") (pintype "passive"))
    )
    (net (code "17") (name "/SD_CMD") (class "Default")
      (node (ref "J3") (pin "3") (pinfunction "CMD_3") (pintype "passive"))
      (node (ref "R40") (pin "2") (pinfunction "2_2") (pintype "passive"))
      (node (ref "U1") (pin "31") (pinfunction "IO38_31") (pintype "passive"))
    )
    (net (code "18") (name "/SD_DAT0") (class "Default")
      (node (ref "J3") (pin "7") (pinfunction "DAT0_7") (pintype "passive"))
      (node (ref "R44") (pin "2") (pinfunction "2_2") (pintype "passive"))
      (node (ref "U1") (pin "32") (pinfunction "IO39_32") (pintype "passive"))
    )
    (net (code "19") (name "/SD_DAT1") (class "Default")
      (node (ref "J3") (pin "8") (pinfunction "DAT1_8") (pintype "passive"))
      (node (ref "R43") (pin "2") (pinfunction "2_2") (pintype "passive"))
      (node (ref "U1") (pin "35") (pinfunction "IO42_35") (pintype "passive"))
    )
    (net (code "20") (name "/SD_DAT2") (class "Default")
      (node (ref "J3") (pin "1") (pinfunction "DAT2_1") (pintype "passive"))
      (node (ref "R42") (pin "2") (pinfunction "2_2") (pintype "passive"))
      (node (ref "U1") (pin "34") (pinfunction "IO41_34") (pintype "passive"))
    )
    (net (code "21") (name "/SD_DAT3") (class "Default")
      (node (ref "J3") (pin "2") (pinfunction "CD/DAT3_2") (pintype "passive"))
      (node (ref "R41") (pin "2") (pinfunction "2_2") (pintype "passive"))
      (node (ref "U1") (pin "33") (pinfunction "IO40_33") (pintype "passive"))
    )
    (net (code "22") (name "/SD_SW") (class "Default")
      (node (ref "J3") (pin "SW-A") (pinfunction "SW-A_SW-A") (pintype "passive"))
      (node (ref "R39") (pin "2") (pinfunction "2_2") (pintype "passive"))
      (node (ref "U1") (pin "15") (pinfunction "IO3_15") (pintype "passive"))
    )
    (net (code "23") (name "/USB_D_N") (class "Default")
      (node (ref "J1") (pin "A7") (pinfunction "DN1_A7") (pintype "passive"))
      (node (ref "J1") (pin "B7") (pinfunction "DN2_B7") (pintype "passive"))
      (node (ref "U3") (pin "1") (pinfunction "1_1") (pintype "passive"))
    )
    (net (code "24") (name "/USB_D_P") (class "Default")
      (node (ref "J1") (pin "A6") (pinfunction "DP1_A6") (pintype "passive"))
      (node (ref "J1") (pin "B6") (pinfunction "DP2_B6") (pintype "passive"))
      (node (ref "U3") (pin "3") (pinfunction "3_3") (pintype "passive"))
    )
    (net (code "25") (name "/VGA_B0") (class "Default")
      (node (ref "R28") (pin "1") (pinfunction "1_1") (pintype "passive"))
      (node (ref "U1") (pin "8") (pinfunction "IO15_8") (pintype "passive"))
    )
    (net (code "26") (name "/VGA_B1") (class "Default")
      (node (ref "R29") (pin "1") (pinfunction "1_1") (pintype "passive"))
      (node (ref "U1") (pin "9") (pinfunction "IO16_9") (pintype "passive"))
    )
    (net (code "27") (name "/VGA_B2") (class "Default")
      (node (ref "R30") (pin "1") (pinfunction "1_1") (pintype "passive"))
      (node (ref "U1") (pin "10") (pinfunction "IO17_10") (pintype "passive"))
    )
    (net (code "28") (name "/VGA_B3") (class "Default")
      (node (ref "R31") (pin "1") (pinfunction "1_1") (pintype "passive"))
      (node (ref "U1") (pin "11") (pinfunction "IO18_11") (pintype "passive"))
    )
    (net (code "29") (name "/VGA_B4") (class "Default")
      (node (ref "R32") (pin "1") (pinfunction "1_1") (pintype "passive"))
      (node (ref "U1") (pin "23") (pinfunction "IO21_23") (pintype "passive"))
    )
    (net (code "30") (name "/VGA_BLUE") (class "Default")
      (node (ref "J2") (pin "3") (pinfunction "3_3") (pintype "passive"))
      (node (ref "R32") (pin "2") (pinfunction "2_2") (pintype "passive"))
      (node (ref "R36") (pin "2") (pinfunction "2_2") (pintype "passive"))
      (node (ref "R38") (pin "1") (pinfunction "1_1") (pintype "passive"))
    )
    (net (code "31") (name "/VGA_G0") (class "Default")
      (node (ref "R16") (pin "1") (pinfunction "1_1") (pintype "passive"))
      (node (ref "U1") (pin "17") (pinfunction "IO9_17") (pintype "passive"))
    )
    (net (code "32") (name "/VGA_G1") (class "Default")
      (node (ref "R17") (pin "1") (pinfunction "1_1") (pintype "passive"))
      (node (ref "U1") (pin "18") (pinfunction "IO10_18") (pintype "passive"))
    )
    (net (code "33") (name "/VGA_G2") (class "Default")
      (node (ref "R18") (pin "1") (pinfunction "1_1") (pintype "passive"))
      (node (ref "U1") (pin "19") (pinfunction "IO11_19") (pintype "passive"))
    )
    (net (code "34") (name "/VGA_G3") (class "Default")
      (node (ref "R19") (pin "1") (pinfunction "1_1") (pintype "passive"))
      (node (ref "U1") (pin "20") (pinfunction "IO12_20") (pintype "passive"))
    )
    (net (code "35") (name "/VGA_G4") (class "Default")
      (node (ref "R20") (pin "1") (pinfunction "1_1") (pintype "passive"))
      (node (ref "U1") (pin "21") (pinfunction "IO13_21") (pintype "passive"))
    )
    (net (code "36") (name "/VGA_G5") (class "Default")
      (node (ref "R27") (pin "1") (pinfunction "1_1") (pintype "passive"))
      (node (ref "U1") (pin "22") (pinfunction "IO14_22") (pintype "passive"))
    )
    (net (code "37") (name "/VGA_GREEN") (class "Default")
      (node (ref "J2") (pin "2") (pinfunction "2_2") (pintype "passive"))
      (node (ref "R27") (pin "2") (pinfunction "2_2") (pintype "passive"))
      (node (ref "R46") (pin "2") (pinfunction "2_2") (pintype "passive"))
      (node (ref "R47") (pin "2") (pinfunction "2_2") (pintype "passive"))
    )
    (net (code "38") (name "/VGA_HSYNC") (class "Default")
      (node (ref "J2") (pin "13") (pinfunction "13_13") (pintype "passive"))
      (node (ref "U1") (pin "39") (pinfunction "IO1_39") (pintype "passive"))
    )
    (net (code "39") (name "/VGA_R0") (class "Default")
      (node (ref "R3") (pin "1") (pinfunction "1_1") (pintype "passive"))
      (node (ref "U1") (pin "4") (pinfunction "IO4_4") (pintype "passive"))
    )
    (net (code "40") (name "/VGA_R1") (class "Default")
      (node (ref "R4") (pin "1") (pinfunction "1_1") (pintype "passive"))
      (node (ref "U1") (pin "5") (pinfunction "IO5_5") (pintype "passive"))
    )
    (net (code "41") (name "/VGA_R2") (class "Default")
      (node (ref "R5") (pin "1") (pinfunction "1_1") (pintype "passive"))
      (node (ref "U1") (pin "6") (pinfunction "IO6_6") (pintype "passive"))
    )
    (net (code "42") (name "/VGA_R3") (class "Default")
      (node (ref "R6") (pin "1") (pinfunction "1_1") (pintype "passive"))
      (node (ref "U1") (pin "7") (pinfunction "IO7_7") (pintype "passive"))
    )
    (net (code "43") (name "/VGA_R4") (class "Default")
      (node (ref "R7") (pin "1") (pinfunction "1_1") (pintype "passive"))
      (node (ref "U1") (pin "12") (pinfunction "IO8_12") (pintype "passive"))
    )
    (net (code "44") (name "/VGA_RED") (class "Default")
      (node (ref "J2") (pin "1") (pinfunction "1_1") (pintype "passive"))
      (node (ref "R12") (pin "2") (pinfunction "2_2") (pintype "passive"))
      (node (ref "R14") (pin "1") (pinfunction "1_1") (pintype "passive"))
      (node (ref "R7") (pin "2") (pinfunction "2_2") (pintype "passive"))
    )
    (net (code "45") (name "/VGA_VSYNC") (class "Default")
      (node (ref "J2") (pin "14") (pinfunction "14_14") (pintype "passive"))
      (node (ref "U1") (pin "38") (pinfunction "IO2_38") (pintype "passive"))
    )
    (net (code "46") (name "GND") (class "Default")
      (node (ref "C10") (pin "1") (pinfunction "1_1") (pintype "passive"))
      (node (ref "C11") (pin "1") (pinfunction "1_1") (pintype "passive"))
      (node (ref "C12") (pin "1") (pinfunction "1_1") (pintype "passive"))
      (node (ref "C13") (pin "1") (pinfunction "1_1") (pintype "passive"))
      (node (ref "C2") (pin "1") (pinfunction "1_1") (pintype "passive"))
      (node (ref "C3") (pin "1") (pinfunction "1_1") (pintype "passive"))
      (node (ref "C4") (pin "2") (pinfunction "2_2") (pintype "passive"))
      (node (ref "C5") (pin "1") (pinfunction "1_1") (pintype "passive"))
      (node (ref "C6") (pin "1") (pinfunction "1_1") (pintype "passive"))
      (node (ref "C7") (pin "1") (pinfunction "1_1") (pintype "passive"))
      (node (ref "C8") (pin "1") (pinfunction "1_1") (pintype "passive"))
      (node (ref "C9") (pin "2") (pinfunction "2_2") (pintype "passive"))
      (node (ref "J1") (pin "A1_B12") (pinfunction "GND_A1_B12") (pintype "passive"))
      (node (ref "J1") (pin "B1_A12") (pinfunction "GND_B1_A12") (pintype "passive"))
      (node (ref "J1") (pin "SH1") (pinfunction "SHELL_GND_SH1") (pintype "passive"))
      (node (ref "J1") (pin "SH2") (pinfunction "SHELL_GND_SH2") (pintype "passive"))
      (node (ref "J1") (pin "SH3") (pinfunction "SHELL_GND_SH3") (pintype "passive"))
      (node (ref "J1") (pin "SH4") (pinfunction "SHELL_GND_SH4") (pintype "passive"))
      (node (ref "J2") (pin "10") (pinfunction "10_10") (pintype "passive"))
      (node (ref "J2") (pin "5") (pinfunction "5_5") (pintype "passive"))
      (node (ref "J2") (pin "6") (pinfunction "6_6") (pintype "passive"))
      (node (ref "J2") (pin "7") (pinfunction "7_7") (pintype "passive"))
      (node (ref "J2") (pin "8") (pinfunction "8_8") (pintype "passive"))
      (node (ref "J2") (pin "S1") (pinfunction "SHELL_GND_S1") (pintype "passive"))
      (node (ref "J2") (pin "S2") (pinfunction "SHELL_GND_S2") (pintype "passive"))
      (node (ref "J3") (pin "6") (pinfunction "VSS_6") (pintype "passive"))
      (node (ref "J3") (pin "S1") (pinfunction "SHIELD_S1") (pintype "passive"))
      (node (ref "J3") (pin "S2") (pinfunction "SHIELD_S2") (pintype "passive"))
      (node (ref "J3") (pin "S3") (pinfunction "SHIELD_S3") (pintype "passive"))
      (node (ref "J3") (pin "S4") (pinfunction "SHIELD_S4") (pintype "passive"))
      (node (ref "J3") (pin "SW-B") (pinfunction "SW-B_SW-B") (pintype "passive"))
      (node (ref "J6") (pin "1") (pinfunction "1_1") (pintype "passive"))
      (node (ref "J6") (pin "2") (pinfunction "2_2") (pintype "passive"))
      (node (ref "J6") (pin "3") (pinfunction "3_3") (pintype "passive"))
      (node (ref "J6") (pin "4") (pinfunction "4_4") (pintype "passive"))
      (node (ref "R1") (pin "1") (pinfunction "1_1") (pintype "passive"))
      (node (ref "R13") (pin "1") (pinfunction "1_1") (pintype "passive"))
      (node (ref "R14") (pin "2") (pinfunction "2_2") (pintype "passive"))
      (node (ref "R2") (pin "1") (pinfunction "1_1") (pintype "passive"))
      (node (ref "R26") (pin "1") (pinfunction "1_1") (pintype "passive"))
      (node (ref "R37") (pin "1") (pinfunction "1_1") (pintype "passive"))
      (node (ref "R38") (pin "2") (pinfunction "2_2") (pintype "passive"))
      (node (ref "R47") (pin "1") (pinfunction "1_1") (pintype "passive"))
      (node (ref "R54") (pin "1") (pinfunction "1_1") (pintype "passive"))
      (node (ref "U1") (pin "1") (pinfunction "GND_1") (pintype "passive"))
      (node (ref "U1") (pin "40") (pinfunction "GND_40") (pintype "passive"))
      (node (ref "U1") (pin "41") (pinfunction "GND_41") (pintype "passive"))
      (node (ref "U2") (pin "4") (pinfunction "GND_4") (pintype "passive"))
      (node (ref "U3") (pin "2") (pinfunction "2_2") (pintype "passive"))
      (node (ref "U4") (pin "29") (pinfunction "GNDPAD_29") (pintype "passive"))
      (node (ref "U4") (pin "3") (pinfunction "GND_3") (pintype "passive"))
    )
    (net (code "47") (name "Net-(D1-Pad2)") (class "Default")
      (node (ref "D1") (pin "2") (pinfunction "2_2") (pintype "passive"))
      (node (ref "R54") (pin "2") (pinfunction "2_2") (pintype "passive"))
    )
    (net (code "48") (name "Net-(J1-CC1)") (class "Default")
      (node (ref "J1") (pin "A5") (pinfunction "CC1_A5") (pintype "passive"))
      (node (ref "R1") (pin "2") (pinfunction "2_2") (pintype "passive"))
    )
    (net (code "49") (name "Net-(J1-CC2)") (class "Default")
      (node (ref "J1") (pin "B5") (pinfunction "CC2_B5") (pintype "passive"))
      (node (ref "R2") (pin "2") (pinfunction "2_2") (pintype "passive"))
    )
    (net (code "50") (name "Net-(Q1-Pad2)") (class "Default")
      (node (ref "Q1") (pin "2") (pinfunction "2_2") (pintype "passive"))
      (node (ref "R53") (pin "1") (pinfunction "1_1") (pintype "passive"))
    )
    (net (code "51") (name "Net-(Q1-Pad5)") (class "Default")
      (node (ref "Q1") (pin "5") (pinfunction "5_5") (pintype "passive"))
      (node (ref "R52") (pin "1") (pinfunction "1_1") (pintype "passive"))
    )
    (net (code "52") (name "Net-(R10-Pad1)") (class "Default")
      (node (ref "R10") (pin "1") (pinfunction "1_1") (pintype "passive"))
      (node (ref "R4") (pin "2") (pinfunction "2_2") (pintype "passive"))
      (node (ref "R9") (pin "2") (pinfunction "2_2") (pintype "passive"))
    )
    (net (code "53") (name "Net-(R10-Pad2)") (class "Default")
      (node (ref "R10") (pin "2") (pinfunction "2_2") (pintype "passive"))
      (node (ref "R11") (pin "1") (pinfunction "1_1") (pintype "passive"))
      (node (ref "R5") (pin "2") (pinfunction "2_2") (pintype "passive"))
    )
    (net (code "54") (name "Net-(R11-Pad2)") (class "Default")
      (node (ref "R11") (pin "2") (pinfunction "2_2") (pintype "passive"))
      (node (ref "R12") (pin "1") (pinfunction "1_1") (pintype "passive"))
      (node (ref "R6") (pin "2") (pinfunction "2_2") (pintype "passive"))
    )
    (net (code "55") (name "Net-(R13-Pad2)") (class "Default")
      (node (ref "R13") (pin "2") (pinfunction "2_2") (pintype "passive"))
      (node (ref "R3") (pin "2") (pinfunction "2_2") (pintype "passive"))
      (node (ref "R9") (pin "1") (pinfunction "1_1") (pintype "passive"))
    )
    (net (code "56") (name "Net-(R16-Pad2)") (class "Default")
      (node (ref "R16") (pin "2") (pinfunction "2_2") (pintype "passive"))
      (node (ref "R22") (pin "1") (pinfunction "1_1") (pintype "passive"))
      (node (ref "R26") (pin "2") (pinfunction "2_2") (pintype "passive"))
    )
    (net (code "57") (name "Net-(R17-Pad2)") (class "Default")
      (node (ref "R17") (pin "2") (pinfunction "2_2") (pintype "passive"))
      (node (ref "R22") (pin "2") (pinfunction "2_2") (pintype "passive"))
      (node (ref "R23") (pin "1") (pinfunction "1_1") (pintype "passive"))
    )
    (net (code "58") (name "Net-(R18-Pad2)") (class "Default")
      (node (ref "R18") (pin "2") (pinfunction "2_2") (pintype "passive"))
      (node (ref "R23") (pin "2") (pinfunction "2_2") (pintype "passive"))
      (node (ref "R24") (pin "1") (pinfunction "1_1") (pintype "passive"))
    )
    (net (code "59") (name "Net-(R19-Pad2)") (class "Default")
      (node (ref "R19") (pin "2") (pinfunction "2_2") (pintype "passive"))
      (node (ref "R24") (pin "2") (pinfunction "2_2") (pintype "passive"))
      (node (ref "R25") (pin "1") (pinfunction "1_1") (pintype "passive"))
    )
    (net (code "60") (name "Net-(R20-Pad2)") (class "Default")
      (node (ref "R20") (pin "2") (pinfunction "2_2") (pintype "passive"))
      (node (ref "R25") (pin "2") (pinfunction "2_2") (pintype "passive"))
      (node (ref "R46") (pin "1") (pinfunction "1_1") (pintype "passive"))
    )
    (net (code "61") (name "Net-(R28-Pad2)") (class "Default")
      (node (ref "R28") (pin "2") (pinfunction "2_2") (pintype "passive"))
      (node (ref "R33") (pin "1") (pinfunction "1_1") (pintype "passive"))
      (node (ref "R37") (pin "2") (pinfunction "2_2") (pintype "passive"))
    )
    (net (code "62") (name "Net-(R29-Pad2)") (class "Default")
      (node (ref "R29") (pin "2") (pinfunction "2_2") (pintype "passive"))
      (node (ref "R33") (pin "2") (pinfunction "2_2") (pintype "passive"))
      (node (ref "R34") (pin "1") (pinfunction "1_1") (pintype "passive"))
    )
    (net (code "63") (name "Net-(R30-Pad2)") (class "Default")
      (node (ref "R30") (pin "2") (pinfunction "2_2") (pintype "passive"))
      (node (ref "R34") (pin "2") (pinfunction "2_2") (pintype "passive"))
      (node (ref "R35") (pin "1") (pinfunction "1_1") (pintype "passive"))
    )
    (net (code "64") (name "Net-(R31-Pad2)") (class "Default")
      (node (ref "R31") (pin "2") (pinfunction "2_2") (pintype "passive"))
      (node (ref "R35") (pin "2") (pinfunction "2_2") (pintype "passive"))
      (node (ref "R36") (pin "1") (pinfunction "1_1") (pintype "passive"))
    )
    (net (code "65") (name "Net-(U1-IO35)") (class "Default")
      (node (ref "TP3") (pin "1") (pinfunction "1_1") (pintype "passive"))
      (node (ref "U1") (pin "28") (pinfunction "IO35_28") (pintype "passive"))
    )
    (net (code "66") (name "Net-(U1-IO36)") (class "Default")
      (node (ref "TP2") (pin "1") (pinfunction "1_1") (pintype "passive"))
      (node (ref "U1") (pin "29") (pinfunction "IO36_29") (pintype "passive"))
    )
    (net (code "67") (name "Net-(U1-IO37)") (class "Default")
      (node (ref "TP1") (pin "1") (pinfunction "1_1") (pintype "passive"))
      (node (ref "U1") (pin "30") (pinfunction "IO37_30") (pintype "passive"))
    )
    (net (code "68") (name "Net-(U2-BST)") (class "Default")
      (node (ref "C1") (pin "2") (pinfunction "2_2") (pintype "passive"))
      (node (ref "U2") (pin "6") (pinfunction "BST_6") (pintype "passive"))
    )
    (net (code "69") (name "Net-(U2-SW)") (class "Default")
      (node (ref "C1") (pin "1") (pinfunction "1_1") (pintype "passive"))
      (node (ref "L1") (pin "1") (pinfunction "1_1") (pintype "passive"))
      (node (ref "U2") (pin "5") (pinfunction "SW_5") (pintype "passive"))
    )
    (net (code "70") (name "Net-(U4-RSTn)") (class "Default")
      (node (ref "R51") (pin "2") (pinfunction "2_2") (pintype "passive"))
      (node (ref "U4") (pin "9") (pinfunction "RSTn_9") (pintype "passive"))
    )
    (net (code "71") (name "unconnected-(J1-SBU1-PadA8)") (class "Default")
      (node (ref "J1") (pin "A8") (pinfunction "SBU1_A8") (pintype "passive+no_connect"))
    )
    (net (code "72") (name "unconnected-(J1-SBU2-PadB8)") (class "Default")
      (node (ref "J1") (pin "B8") (pinfunction "SBU2_B8") (pintype "passive+no_connect"))
    )
    (net (code "73") (name "unconnected-(J2-Pad4)") (class "Default")
      (node (ref "J2") (pin "4") (pinfunction "4_4") (pintype "passive+no_connect"))
    )
    (net (code "74") (name "unconnected-(J2-Pad11)") (class "Default")
      (node (ref "J2") (pin "11") (pinfunction "11_11") (pintype "passive+no_connect"))
    )
    (net (code "75") (name "unconnected-(J2-Pad12)") (class "Default")
      (node (ref "J2") (pin "12") (pinfunction "12_12") (pintype "passive+no_connect"))
    )
    (net (code "76") (name "unconnected-(J2-Pad15)") (class "Default")
      (node (ref "J2") (pin "15") (pinfunction "15_15") (pintype "passive+no_connect"))
    )
    (net (code "77") (name "unconnected-(U4-CHR0-Pad15)") (class "Default")
      (node (ref "U4") (pin "15") (pinfunction "CHR0_15") (pintype "passive+no_connect"))
    )
    (net (code "78") (name "unconnected-(U4-CHR1-Pad14)") (class "Default")
      (node (ref "U4") (pin "14") (pinfunction "CHR1_14") (pintype "passive+no_connect"))
    )
    (net (code "79") (name "unconnected-(U4-CHREN-Pad13)") (class "Default")
      (node (ref "U4") (pin "13") (pinfunction "CHREN_13") (pintype "passive+no_connect"))
    )
    (net (code "80") (name "unconnected-(U4-CTS-Pad23)") (class "Default")
      (node (ref "U4") (pin "23") (pinfunction "CTS_23") (pintype "passive+no_connect"))
    )
    (net (code "81") (name "unconnected-(U4-DCD-Pad1)") (class "Default")
      (node (ref "U4") (pin "1") (pinfunction "DCD_1") (pintype "passive+no_connect"))
    )
    (net (code "82") (name "unconnected-(U4-DSR-Pad27)") (class "Default")
      (node (ref "U4") (pin "27") (pinfunction "DSR_27") (pintype "passive+no_connect"))
    )
    (net (code "83") (name "unconnected-(U4-GPIO.0_{slash}_TXT-Pad19)") (class "Default")
      (node (ref "U4") (pin "19") (pinfunction "GPIO.0_/_TXT_19") (pintype "passive+no_connect"))
    )
    (net (code "84") (name "unconnected-(U4-GPIO.1_{slash}_RXT-Pad18)") (class "Default")
      (node (ref "U4") (pin "18") (pinfunction "GPIO.1_/_RXT_18") (pintype "passive+no_connect"))
    )
    (net (code "85") (name "unconnected-(U4-GPIO.2_{slash}_RS485-Pad17)") (class "Default")
      (node (ref "U4") (pin "17") (pinfunction "GPIO.2_/_RS485_17") (pintype "passive+no_connect"))
    )
    (net (code "86") (name "unconnected-(U4-GPIO.3_{slash}_WAKEUP-Pad16)") (class "Default")
      (node (ref "U4") (pin "16") (pinfunction "GPIO.3_/_WAKEUP_16") (pintype "passive+no_connect"))
    )
    (net (code "87") (name "unconnected-(U4-GPIO.4-Pad22)") (class "Default")
      (node (ref "U4") (pin "22") (pinfunction "GPIO.4_22") (pintype "passive+no_connect"))
    )
    (net (code "88") (name "unconnected-(U4-GPIO.5-Pad21)") (class "Default")
      (node (ref "U4") (pin "21") (pinfunction "GPIO.5_21") (pintype "passive+no_connect"))
    )
    (net (code "89") (name "unconnected-(U4-GPIO.6-Pad20)") (class "Default")
      (node (ref "U4") (pin "20") (pinfunction "GPIO.6_20") (pintype "passive+no_connect"))
    )
    (net (code "90") (name "unconnected-(U4-NC-Pad10)") (class "Default")
      (node (ref "U4") (pin "10") (pinfunction "NC_10") (pintype "passive+no_connect"))
    )
    (net (code "91") (name "unconnected-(U4-RI{slash}CLK-Pad2)") (class "Default")
      (node (ref "U4") (pin "2") (pinfunction "RI/CLK_2") (pintype "passive+no_connect"))
    )
    (net (code "92") (name "unconnected-(U4-SUSPEND-Pad12)") (class "Default")
      (node (ref "U4") (pin "12") (pinfunction "SUSPEND_12") (pintype "passive+no_connect"))
    )
    (net (code "93") (name "unconnected-(U4-SUSPENDn-Pad11)") (class "Default")
      (node (ref "U4") (pin "11") (pinfunction "SUSPENDn_11") (pintype "passive+no_connect"))
    )
  )
)
